# daughterboard.net
KiCad netlist of a schematic drawn in EAGLE
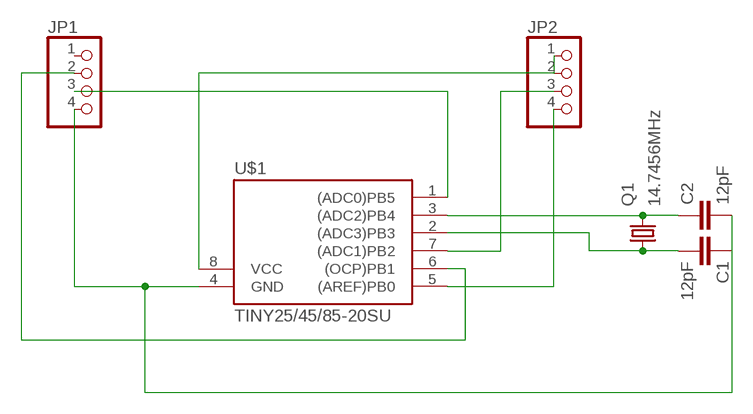
[diagram p0: schematic, sheet 1]

(export (version "E")
  (design (tool "Eeschema 10.0.6"))
  (components
    (comp (ref "C1")
      (value "12pF")
      (footprint "eagle-import:C0805")
      (libsource (lib "eagle-import") (part "C-EUC0805"))
    )
    (comp (ref "C2")
      (value "12pF")
      (footprint "eagle-import:C0805")
      (libsource (lib "eagle-import") (part "C-EUC0805"))
    )
    (comp (ref "JP1")
      (value "PINHD-1X4")
      (footprint "eagle-import:1X04")
      (libsource (lib "eagle-import") (part "PINHD-1X4"))
    )
    (comp (ref "JP2")
      (value "PINHD-1X4")
      (footprint "eagle-import:1X04")
      (libsource (lib "eagle-import") (part "PINHD-1X4"))
    )
    (comp (ref "Q1")
      (value "14.7456MHz")
      (footprint "eagle-import:3.2X2.5_KX-7")
      (libsource (lib "eagle-import") (part "KX-7"))
    )
    (comp (ref "U$1")
      (value "TINY25/45/85-20SU")
      (footprint "eagle-import:SOIC8")
      (libsource (lib "eagle-import") (part "TINY25/45/85-20SU"))
    )
  )
  (nets
    (net (code "1") (name "Net-(Q1-2)") (class "Default")
      (node (ref "C2") (pin "1") (pinfunction "1_1") (pintype "passive"))
      (node (ref "Q1") (pin "3") (pinfunction "2_3") (pintype "passive"))
      (node (ref "U$1") (pin "3") (pinfunction "(ADC2)PB4_3") (pintype "bidirectional"))
    )
    (net (code "2") (name "Net-(U$1-(ADC0)PB5)") (class "Default")
      (node (ref "JP1") (pin "3") (pinfunction "3_3") (pintype "passive"))
      (node (ref "U$1") (pin "1") (pinfunction "(ADC0)PB5_1") (pintype "bidirectional"))
    )
    (net (code "3") (name "Net-(U$1-(ADC1)PB2)") (class "Default")
      (node (ref "JP2") (pin "3") (pinfunction "3_3") (pintype "passive"))
      (node (ref "U$1") (pin "7") (pinfunction "(ADC1)PB2_7") (pintype "bidirectional"))
    )
    (net (code "4") (name "Net-(U$1-(ADC3)PB3)") (class "Default")
      (node (ref "C1") (pin "2") (pinfunction "2_2") (pintype "passive"))
      (node (ref "Q1") (pin "1") (pinfunction "1_1") (pintype "passive"))
      (node (ref "U$1") (pin "2") (pinfunction "(ADC3)PB3_2") (pintype "bidirectional"))
    )
    (net (code "5") (name "Net-(U$1-(AREF)PB0)") (class "Default")
      (node (ref "JP2") (pin "4") (pinfunction "4_4") (pintype "passive"))
      (node (ref "U$1") (pin "5") (pinfunction "(AREF)PB0_5") (pintype "bidirectional"))
    )
    (net (code "6") (name "Net-(U$1-(OCP)PB1)") (class "Default")
      (node (ref "JP1") (pin "2") (pinfunction "2_2") (pintype "passive"))
      (node (ref "U$1") (pin "6") (pinfunction "(OCP)PB1_6") (pintype "bidirectional"))
    )
    (net (code "7") (name "Net-(U$1-GND)") (class "Default")
      (node (ref "C1") (pin "1") (pinfunction "1_1") (pintype "passive"))
      (node (ref "C2") (pin "2") (pinfunction "2_2") (pintype "passive"))
      (node (ref "JP1") (pin "4") (pinfunction "4_4") (pintype "passive"))
      (node (ref "U$1") (pin "4") (pinfunction "GND_4") (pintype "power_in"))
    )
    (net (code "8") (name "Net-(U$1-VCC)") (class "Default")
      (node (ref "JP2") (pin "1") (pinfunction "1_1") (pintype "passive"))
      (node (ref "JP2") (pin "2") (pinfunction "2_2") (pintype "passive"))
      (node (ref "U$1") (pin "8") (pinfunction "VCC_8") (pintype "power_in"))
    )
    (net (code "9") (name "unconnected-(JP1-Pad1)") (class "Default")
      (node (ref "JP1") (pin "1") (pinfunction "1_1") (pintype "passive"))
    )
  )
)
